# Oscillator_Core_Sch.net
KiCad netlist of a schematic drawn in EAGLE
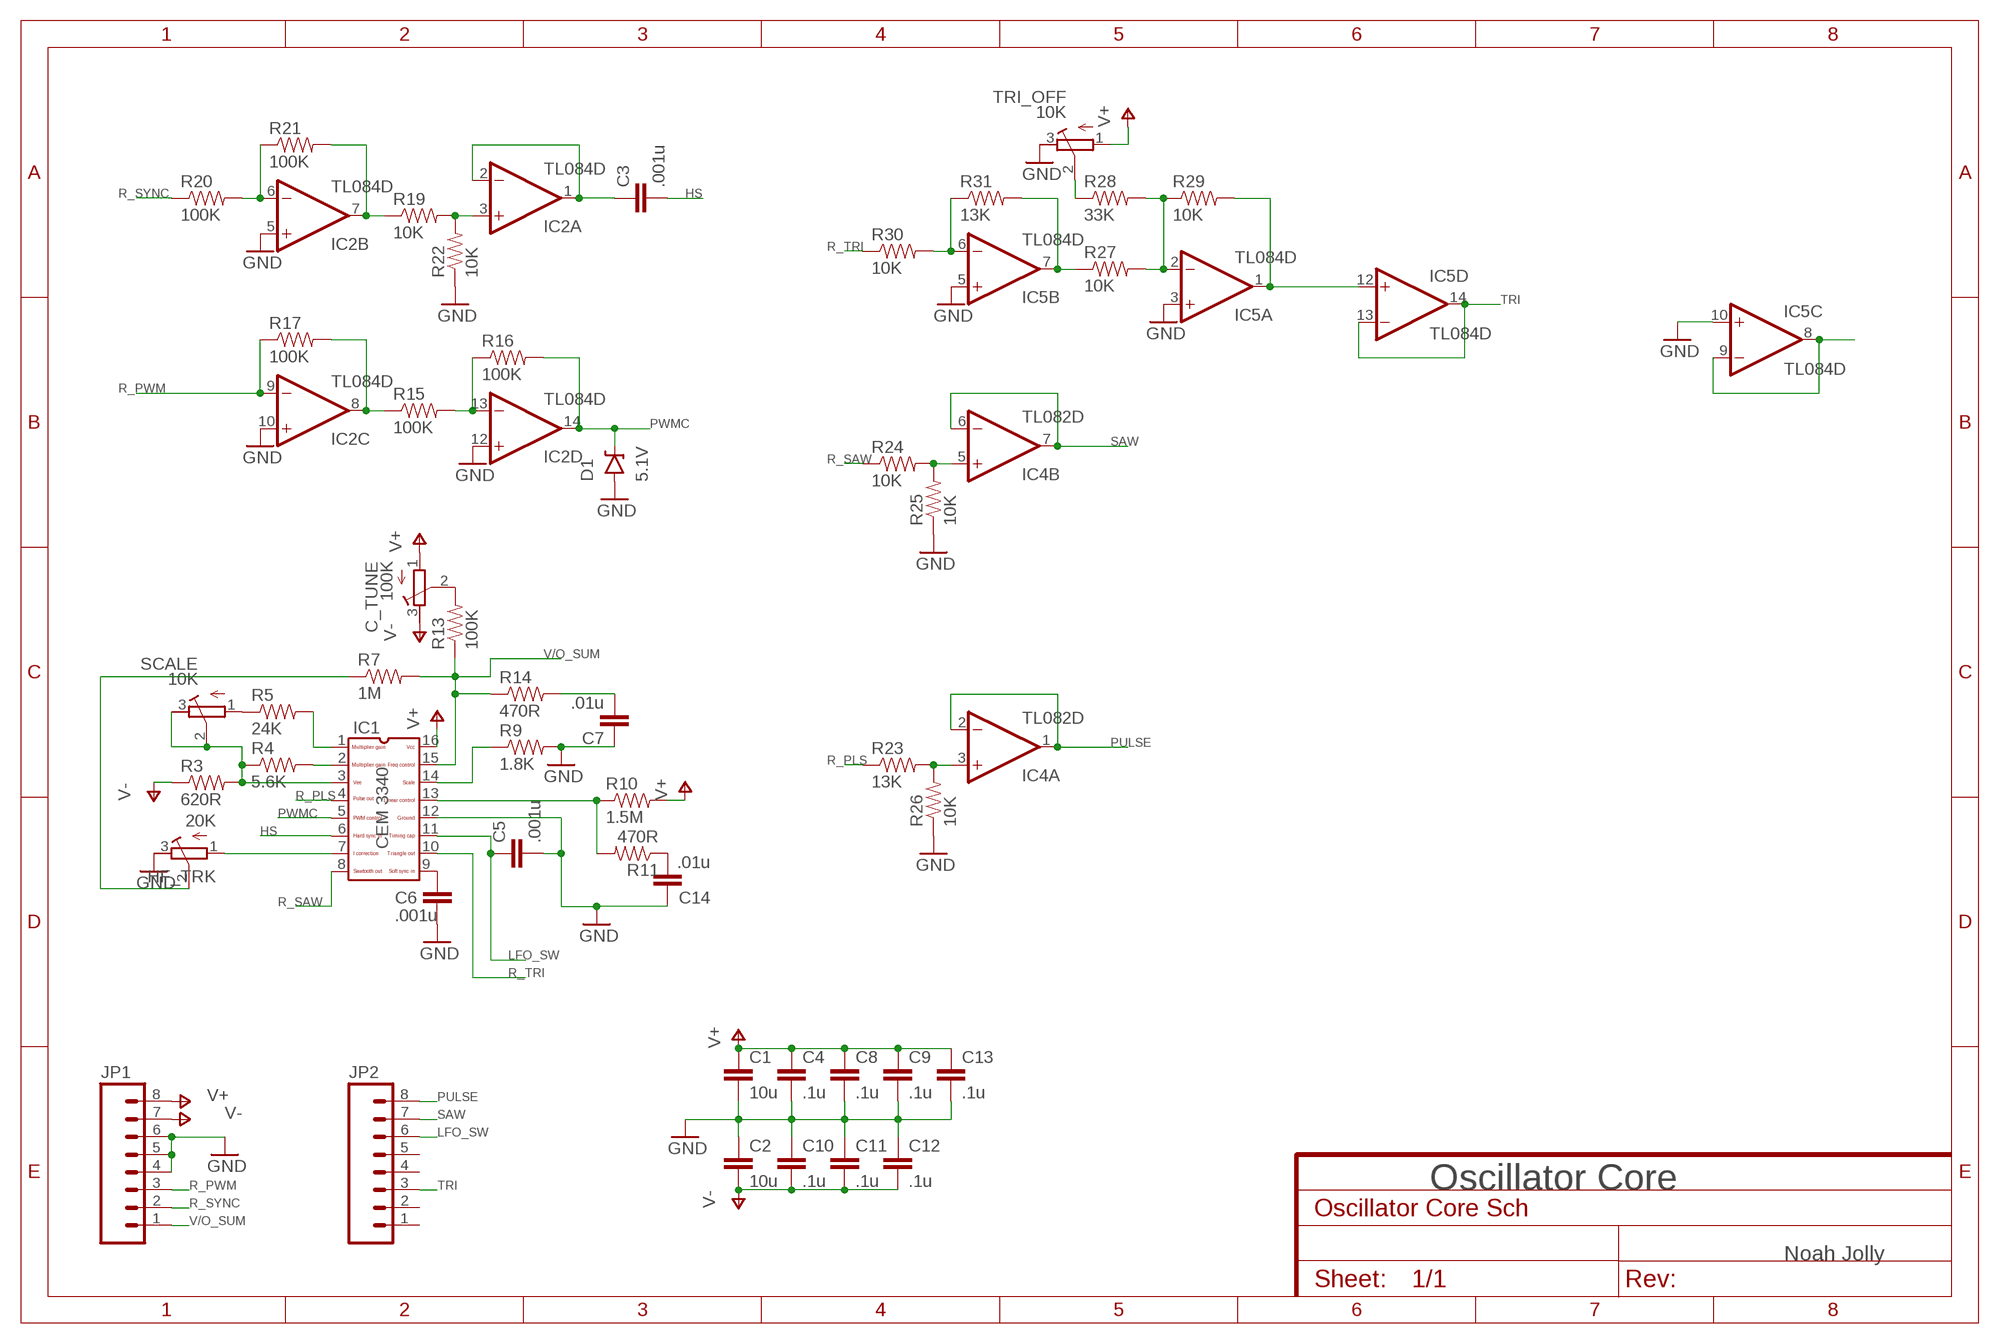
[diagram p0: schematic, sheet 1]

(export (version "E")
  (design (tool "Eeschema 10.0.6"))
  (components
    (comp (ref "C1")
      (value "10u")
      (footprint "eagle-import:1206")
      (libsource (lib "eagle-import") (part "CAP1206"))
    )
    (comp (ref "C2")
      (value "10u")
      (footprint "eagle-import:1206")
      (libsource (lib "eagle-import") (part "CAP1206"))
    )
    (comp (ref "C3")
      (value ".001u")
      (footprint "eagle-import:0805")
      (libsource (lib "eagle-import") (part "CAP0805"))
    )
    (comp (ref "C4")
      (value ".1u")
      (footprint "eagle-import:0805")
      (libsource (lib "eagle-import") (part "CAP0805"))
    )
    (comp (ref "C5")
      (value ".001u")
      (footprint "eagle-import:CAP-PTH-5MM")
      (libsource (lib "eagle-import") (part "SparkFun-Passives_CAPPTH1"))
    )
    (comp (ref "C6")
      (value ".001u")
      (footprint "eagle-import:0805")
      (libsource (lib "eagle-import") (part "CAP0805"))
    )
    (comp (ref "C7")
      (value ".01u")
      (footprint "eagle-import:0805")
      (libsource (lib "eagle-import") (part "CAP0805"))
    )
    (comp (ref "C8")
      (value ".1u")
      (footprint "eagle-import:0805")
      (libsource (lib "eagle-import") (part "CAP0805"))
    )
    (comp (ref "C9")
      (value ".1u")
      (footprint "eagle-import:0805")
      (libsource (lib "eagle-import") (part "CAP0805"))
    )
    (comp (ref "C10")
      (value ".1u")
      (footprint "eagle-import:0805")
      (libsource (lib "eagle-import") (part "CAP0805"))
    )
    (comp (ref "C11")
      (value ".1u")
      (footprint "eagle-import:0805")
      (libsource (lib "eagle-import") (part "CAP0805"))
    )
    (comp (ref "C12")
      (value ".1u")
      (footprint "eagle-import:0805")
      (libsource (lib "eagle-import") (part "CAP0805"))
    )
    (comp (ref "C13")
      (value ".1u")
      (footprint "eagle-import:0805")
      (libsource (lib "eagle-import") (part "CAP0805"))
    )
    (comp (ref "C14")
      (value ".01u")
      (footprint "eagle-import:0805")
      (libsource (lib "eagle-import") (part "CAP0805"))
    )
    (comp (ref "C_TUNE")
      (value "100K")
      (footprint "eagle-import:RTRIM3296Y")
      (libsource (lib "eagle-import") (part "R-TRIMM3296Y"))
    )
    (comp (ref "D1")
      (value "5.1V")
      (footprint "eagle-import:SOD-123")
      (libsource (lib "eagle-import") (part "DIODE-ZENER16V"))
    )
    (comp (ref "HF_TRK")
      (value "20K")
      (footprint "eagle-import:RTRIM3296Y")
      (libsource (lib "eagle-import") (part "R-TRIMM3296Y"))
    )
    (comp (ref "IC1")
      (value "CEM3340")
      (footprint "eagle-import:DIL16")
      (libsource (lib "eagle-import") (part "CEM3340"))
    )
    (comp (ref "IC2")
      (value "TL084D")
      (footprint "eagle-import:SO14")
      (libsource (lib "eagle-import") (part "TL084D"))
    )
    (comp (ref "IC4")
      (value "TL082D")
      (footprint "eagle-import:SO08")
      (libsource (lib "eagle-import") (part "TL082D"))
    )
    (comp (ref "IC5")
      (value "TL084D")
      (footprint "eagle-import:SO14")
      (libsource (lib "eagle-import") (part "TL084D"))
    )
    (comp (ref "JP1")
      (value "M08")
      (footprint "eagle-import:1X08_ROUND")
      (libsource (lib "eagle-import") (part "M08"))
    )
    (comp (ref "JP2")
      (value "M08")
      (footprint "eagle-import:1X08_ROUND")
      (libsource (lib "eagle-import") (part "M08"))
    )
    (comp (ref "R3")
      (value "620R")
      (footprint "eagle-import:0805@1")
      (libsource (lib "eagle-import") (part "RESISTOR0805-RES"))
    )
    (comp (ref "R4")
      (value "5.6K")
      (footprint "eagle-import:0805@1")
      (libsource (lib "eagle-import") (part "RESISTOR0805-RES"))
    )
    (comp (ref "R5")
      (value "24K")
      (footprint "eagle-import:0805@1")
      (libsource (lib "eagle-import") (part "RESISTOR0805-RES"))
    )
    (comp (ref "R7")
      (value "1M")
      (footprint "eagle-import:0805@1")
      (libsource (lib "eagle-import") (part "RESISTOR0805-RES"))
    )
    (comp (ref "R9")
      (value "1.8K")
      (footprint "eagle-import:0805@1")
      (libsource (lib "eagle-import") (part "RESISTOR0805-RES"))
    )
    (comp (ref "R10")
      (value "1.5M")
      (footprint "eagle-import:0805@1")
      (libsource (lib "eagle-import") (part "RESISTOR0805-RES"))
    )
    (comp (ref "R11")
      (value "470R")
      (footprint "eagle-import:0805@1")
      (libsource (lib "eagle-import") (part "RESISTOR0805-RES"))
    )
    (comp (ref "R13")
      (value "100K")
      (footprint "eagle-import:0805@1")
      (libsource (lib "eagle-import") (part "RESISTOR0805-RES"))
    )
    (comp (ref "R14")
      (value "470R")
      (footprint "eagle-import:0805@1")
      (libsource (lib "eagle-import") (part "RESISTOR0805-RES"))
    )
    (comp (ref "R15")
      (value "100K")
      (footprint "eagle-import:0805@1")
      (libsource (lib "eagle-import") (part "RESISTOR0805-RES"))
    )
    (comp (ref "R16")
      (value "100K")
      (footprint "eagle-import:0805@1")
      (libsource (lib "eagle-import") (part "RESISTOR0805-RES"))
    )
    (comp (ref "R17")
      (value "100K")
      (footprint "eagle-import:0805@1")
      (libsource (lib "eagle-import") (part "RESISTOR0805-RES"))
    )
    (comp (ref "R19")
      (value "10K")
      (footprint "eagle-import:0805@1")
      (libsource (lib "eagle-import") (part "RESISTOR0805-RES"))
    )
    (comp (ref "R20")
      (value "100K")
      (footprint "eagle-import:0805@1")
      (libsource (lib "eagle-import") (part "RESISTOR0805-RES"))
    )
    (comp (ref "R21")
      (value "100K")
      (footprint "eagle-import:0805@1")
      (libsource (lib "eagle-import") (part "RESISTOR0805-RES"))
    )
    (comp (ref "R22")
      (value "10K")
      (footprint "eagle-import:0805@1")
      (libsource (lib "eagle-import") (part "RESISTOR0805-RES"))
    )
    (comp (ref "R23")
      (value "13K")
      (footprint "eagle-import:0805@1")
      (libsource (lib "eagle-import") (part "RESISTOR0805-RES"))
    )
    (comp (ref "R24")
      (value "10K")
      (footprint "eagle-import:0805@1")
      (libsource (lib "eagle-import") (part "RESISTOR0805-RES"))
    )
    (comp (ref "R25")
      (value "10K")
      (footprint "eagle-import:0805@1")
      (libsource (lib "eagle-import") (part "RESISTOR0805-RES"))
    )
    (comp (ref "R26")
      (value "10K")
      (footprint "eagle-import:0805@1")
      (libsource (lib "eagle-import") (part "RESISTOR0805-RES"))
    )
    (comp (ref "R27")
      (value "10K")
      (footprint "eagle-import:0805@1")
      (libsource (lib "eagle-import") (part "RESISTOR0805-RES"))
    )
    (comp (ref "R28")
      (value "33K")
      (footprint "eagle-import:0805@1")
      (libsource (lib "eagle-import") (part "RESISTOR0805-RES"))
    )
    (comp (ref "R29")
      (value "10K")
      (footprint "eagle-import:0805@1")
      (libsource (lib "eagle-import") (part "RESISTOR0805-RES"))
    )
    (comp (ref "R30")
      (value "10K")
      (footprint "eagle-import:0805@1")
      (libsource (lib "eagle-import") (part "RESISTOR0805-RES"))
    )
    (comp (ref "R31")
      (value "13K")
      (footprint "eagle-import:0805@1")
      (libsource (lib "eagle-import") (part "RESISTOR0805-RES"))
    )
    (comp (ref "SCALE")
      (value "10K")
      (footprint "eagle-import:RTRIM3296Y")
      (libsource (lib "eagle-import") (part "R-TRIMM3296Y"))
    )
    (comp (ref "TRI_OFF")
      (value "10K")
      (footprint "eagle-import:RTRIM3296Y")
      (libsource (lib "eagle-import") (part "R-TRIMM3296Y"))
    )
  )
  (nets
    (net (code "1") (name "/HS") (class "Default")
      (node (ref "C3") (pin "2") (pinfunction "2_2") (pintype "passive"))
      (node (ref "IC1") (pin "6") (pinfunction "6_6") (pintype "input"))
    )
    (net (code "2") (name "/LFO_SW") (class "Default")
      (node (ref "C5") (pin "1") (pinfunction "1_1") (pintype "passive"))
      (node (ref "IC1") (pin "11") (pinfunction "11_11") (pintype "bidirectional"))
      (node (ref "JP2") (pin "6") (pinfunction "6_6") (pintype "passive"))
    )
    (net (code "3") (name "/PULSE") (class "Default")
      (node (ref "IC4") (pin "1") (pinfunction "OUT_1") (pintype "output"))
      (node (ref "IC4") (pin "2") (pinfunction "-IN_2") (pintype "input"))
      (node (ref "JP2") (pin "8") (pinfunction "8_8") (pintype "passive"))
    )
    (net (code "4") (name "/PWMC") (class "Default")
      (node (ref "D1") (pin "C") (pinfunction "C_C") (pintype "passive"))
      (node (ref "IC1") (pin "5") (pinfunction "5_5") (pintype "input"))
      (node (ref "IC2") (pin "14") (pinfunction "OUT_14") (pintype "output"))
      (node (ref "R16") (pin "2") (pinfunction "2_2") (pintype "passive"))
    )
    (net (code "5") (name "/R_PLS") (class "Default")
      (node (ref "IC1") (pin "4") (pinfunction "4_4") (pintype "output"))
      (node (ref "R23") (pin "1") (pinfunction "1_1") (pintype "passive"))
    )
    (net (code "6") (name "/R_PWM") (class "Default")
      (node (ref "IC2") (pin "9") (pinfunction "-IN_9") (pintype "input"))
      (node (ref "JP1") (pin "3") (pinfunction "3_3") (pintype "passive"))
      (node (ref "R17") (pin "1") (pinfunction "1_1") (pintype "passive"))
    )
    (net (code "7") (name "/R_SAW") (class "Default")
      (node (ref "IC1") (pin "8") (pinfunction "8_8") (pintype "output"))
      (node (ref "R24") (pin "1") (pinfunction "1_1") (pintype "passive"))
    )
    (net (code "8") (name "/R_SYNC") (class "Default")
      (node (ref "JP1") (pin "2") (pinfunction "2_2") (pintype "passive"))
      (node (ref "R20") (pin "1") (pinfunction "1_1") (pintype "passive"))
    )
    (net (code "9") (name "/R_TRI") (class "Default")
      (node (ref "IC1") (pin "10") (pinfunction "10_10") (pintype "output"))
      (node (ref "R30") (pin "1") (pinfunction "1_1") (pintype "passive"))
    )
    (net (code "10") (name "/SAW") (class "Default")
      (node (ref "IC4") (pin "6") (pinfunction "-IN_6") (pintype "input"))
      (node (ref "IC4") (pin "7") (pinfunction "OUT_7") (pintype "output"))
      (node (ref "JP2") (pin "7") (pinfunction "7_7") (pintype "passive"))
    )
    (net (code "11") (name "/TRI") (class "Default")
      (node (ref "IC5") (pin "13") (pinfunction "-IN_13") (pintype "input"))
      (node (ref "IC5") (pin "14") (pinfunction "OUT_14") (pintype "output"))
      (node (ref "JP2") (pin "3") (pinfunction "3_3") (pintype "passive"))
    )
    (net (code "12") (name "/V{slash}O_SUM") (class "Default")
      (node (ref "IC1") (pin "15") (pinfunction "15_15") (pintype "input"))
      (node (ref "JP1") (pin "1") (pinfunction "1_1") (pintype "passive"))
      (node (ref "R13") (pin "1") (pinfunction "1_1") (pintype "passive"))
      (node (ref "R14") (pin "1") (pinfunction "1_1") (pintype "passive"))
      (node (ref "R7") (pin "2") (pinfunction "2_2") (pintype "passive"))
    )
    (net (code "13") (name "GND") (class "Default")
      (node (ref "C1") (pin "2") (pinfunction "2_2") (pintype "passive"))
      (node (ref "C10") (pin "1") (pinfunction "1_1") (pintype "passive"))
      (node (ref "C11") (pin "1") (pinfunction "1_1") (pintype "passive"))
      (node (ref "C12") (pin "1") (pinfunction "1_1") (pintype "passive"))
      (node (ref "C13") (pin "2") (pinfunction "2_2") (pintype "passive"))
      (node (ref "C14") (pin "1") (pinfunction "1_1") (pintype "passive"))
      (node (ref "C2") (pin "1") (pinfunction "1_1") (pintype "passive"))
      (node (ref "C4") (pin "2") (pinfunction "2_2") (pintype "passive"))
      (node (ref "C5") (pin "2") (pinfunction "2_2") (pintype "passive"))
      (node (ref "C6") (pin "2") (pinfunction "2_2") (pintype "passive"))
      (node (ref "C7") (pin "1") (pinfunction "1_1") (pintype "passive"))
      (node (ref "C8") (pin "2") (pinfunction "2_2") (pintype "passive"))
      (node (ref "C9") (pin "2") (pinfunction "2_2") (pintype "passive"))
      (node (ref "D1") (pin "A") (pinfunction "A_A") (pintype "passive"))
      (node (ref "HF_TRK") (pin "3") (pinfunction "E_3") (pintype "passive"))
      (node (ref "IC1") (pin "12") (pinfunction "12_12") (pintype "power_in"))
      (node (ref "IC2") (pin "10") (pinfunction "+IN_10") (pintype "input"))
      (node (ref "IC2") (pin "12") (pinfunction "+IN_12") (pintype "input"))
      (node (ref "IC2") (pin "5") (pinfunction "+IN_5") (pintype "input"))
      (node (ref "IC5") (pin "10") (pinfunction "+IN_10") (pintype "input"))
      (node (ref "IC5") (pin "3") (pinfunction "+IN_3") (pintype "input"))
      (node (ref "IC5") (pin "5") (pinfunction "+IN_5") (pintype "input"))
      (node (ref "JP1") (pin "4") (pinfunction "4_4") (pintype "passive"))
      (node (ref "JP1") (pin "5") (pinfunction "5_5") (pintype "passive"))
      (node (ref "JP1") (pin "6") (pinfunction "6_6") (pintype "passive"))
      (node (ref "R22") (pin "1") (pinfunction "1_1") (pintype "passive"))
      (node (ref "R25") (pin "1") (pinfunction "1_1") (pintype "passive"))
      (node (ref "R26") (pin "1") (pinfunction "1_1") (pintype "passive"))
      (node (ref "R9") (pin "2") (pinfunction "2_2") (pintype "passive"))
      (node (ref "TRI_OFF") (pin "3") (pinfunction "E_3") (pintype "passive"))
    )
    (net (code "14") (name "Net-(C6-Pad1)") (class "Default")
      (node (ref "C6") (pin "1") (pinfunction "1_1") (pintype "passive"))
      (node (ref "IC1") (pin "9") (pinfunction "9_9") (pintype "input"))
    )
    (net (code "15") (name "Net-(C7-Pad2)") (class "Default")
      (node (ref "C7") (pin "2") (pinfunction "2_2") (pintype "passive"))
      (node (ref "R14") (pin "2") (pinfunction "2_2") (pintype "passive"))
    )
    (net (code "16") (name "Net-(C14-Pad2)") (class "Default")
      (node (ref "C14") (pin "2") (pinfunction "2_2") (pintype "passive"))
      (node (ref "R11") (pin "1") (pinfunction "1_1") (pintype "passive"))
    )
    (net (code "17") (name "Net-(C_TUNE-S)") (class "Default")
      (node (ref "C_TUNE") (pin "2") (pinfunction "S_2") (pintype "passive"))
      (node (ref "R13") (pin "2") (pinfunction "2_2") (pintype "passive"))
    )
    (net (code "18") (name "Net-(HF_TRK-A)") (class "Default")
      (node (ref "HF_TRK") (pin "1") (pinfunction "A_1") (pintype "passive"))
      (node (ref "IC1") (pin "7") (pinfunction "7_7") (pintype "bidirectional"))
    )
    (net (code "19") (name "Net-(HF_TRK-S)") (class "Default")
      (node (ref "HF_TRK") (pin "2") (pinfunction "S_2") (pintype "passive"))
      (node (ref "R7") (pin "1") (pinfunction "1_1") (pintype "passive"))
    )
    (net (code "20") (name "Net-(IC1-Pad1)") (class "Default")
      (node (ref "IC1") (pin "1") (pinfunction "1_1") (pintype "bidirectional"))
      (node (ref "R5") (pin "2") (pinfunction "2_2") (pintype "passive"))
    )
    (net (code "21") (name "Net-(IC1-Pad2)") (class "Default")
      (node (ref "IC1") (pin "2") (pinfunction "2_2") (pintype "bidirectional"))
      (node (ref "R4") (pin "2") (pinfunction "2_2") (pintype "passive"))
    )
    (net (code "22") (name "Net-(IC1-Pad13)") (class "Default")
      (node (ref "IC1") (pin "13") (pinfunction "13_13") (pintype "input"))
      (node (ref "R10") (pin "1") (pinfunction "1_1") (pintype "passive"))
      (node (ref "R11") (pin "2") (pinfunction "2_2") (pintype "passive"))
    )
    (net (code "23") (name "Net-(IC1-Pad14)") (class "Default")
      (node (ref "IC1") (pin "14") (pinfunction "14_14") (pintype "input"))
      (node (ref "R9") (pin "1") (pinfunction "1_1") (pintype "passive"))
    )
    (net (code "24") (name "Net-(IC2A-+IN)") (class "Default")
      (node (ref "IC2") (pin "3") (pinfunction "+IN_3") (pintype "input"))
      (node (ref "R19") (pin "2") (pinfunction "2_2") (pintype "passive"))
      (node (ref "R22") (pin "2") (pinfunction "2_2") (pintype "passive"))
    )
    (net (code "25") (name "Net-(IC2A--IN)") (class "Default")
      (node (ref "C3") (pin "1") (pinfunction "1_1") (pintype "passive"))
      (node (ref "IC2") (pin "1") (pinfunction "OUT_1") (pintype "output"))
      (node (ref "IC2") (pin "2") (pinfunction "-IN_2") (pintype "input"))
    )
    (net (code "26") (name "Net-(IC2B--IN)") (class "Default")
      (node (ref "IC2") (pin "6") (pinfunction "-IN_6") (pintype "input"))
      (node (ref "R20") (pin "2") (pinfunction "2_2") (pintype "passive"))
      (node (ref "R21") (pin "1") (pinfunction "1_1") (pintype "passive"))
    )
    (net (code "27") (name "Net-(IC2B-OUT)") (class "Default")
      (node (ref "IC2") (pin "7") (pinfunction "OUT_7") (pintype "output"))
      (node (ref "R19") (pin "1") (pinfunction "1_1") (pintype "passive"))
      (node (ref "R21") (pin "2") (pinfunction "2_2") (pintype "passive"))
    )
    (net (code "28") (name "Net-(IC2C-OUT)") (class "Default")
      (node (ref "IC2") (pin "8") (pinfunction "OUT_8") (pintype "output"))
      (node (ref "R15") (pin "1") (pinfunction "1_1") (pintype "passive"))
      (node (ref "R17") (pin "2") (pinfunction "2_2") (pintype "passive"))
    )
    (net (code "29") (name "Net-(IC2D--IN)") (class "Default")
      (node (ref "IC2") (pin "13") (pinfunction "-IN_13") (pintype "input"))
      (node (ref "R15") (pin "2") (pinfunction "2_2") (pintype "passive"))
      (node (ref "R16") (pin "1") (pinfunction "1_1") (pintype "passive"))
    )
    (net (code "30") (name "Net-(IC4A-+IN)") (class "Default")
      (node (ref "IC4") (pin "3") (pinfunction "+IN_3") (pintype "input"))
      (node (ref "R23") (pin "2") (pinfunction "2_2") (pintype "passive"))
      (node (ref "R26") (pin "2") (pinfunction "2_2") (pintype "passive"))
    )
    (net (code "31") (name "Net-(IC4B-+IN)") (class "Default")
      (node (ref "IC4") (pin "5") (pinfunction "+IN_5") (pintype "input"))
      (node (ref "R24") (pin "2") (pinfunction "2_2") (pintype "passive"))
      (node (ref "R25") (pin "2") (pinfunction "2_2") (pintype "passive"))
    )
    (net (code "32") (name "Net-(IC5A--IN)") (class "Default")
      (node (ref "IC5") (pin "2") (pinfunction "-IN_2") (pintype "input"))
      (node (ref "R27") (pin "2") (pinfunction "2_2") (pintype "passive"))
      (node (ref "R28") (pin "2") (pinfunction "2_2") (pintype "passive"))
      (node (ref "R29") (pin "1") (pinfunction "1_1") (pintype "passive"))
    )
    (net (code "33") (name "Net-(IC5A-OUT)") (class "Default")
      (node (ref "IC5") (pin "1") (pinfunction "OUT_1") (pintype "output"))
      (node (ref "IC5") (pin "12") (pinfunction "+IN_12") (pintype "input"))
      (node (ref "R29") (pin "2") (pinfunction "2_2") (pintype "passive"))
    )
    (net (code "34") (name "Net-(IC5B--IN)") (class "Default")
      (node (ref "IC5") (pin "6") (pinfunction "-IN_6") (pintype "input"))
      (node (ref "R30") (pin "2") (pinfunction "2_2") (pintype "passive"))
      (node (ref "R31") (pin "1") (pinfunction "1_1") (pintype "passive"))
    )
    (net (code "35") (name "Net-(IC5B-OUT)") (class "Default")
      (node (ref "IC5") (pin "7") (pinfunction "OUT_7") (pintype "output"))
      (node (ref "R27") (pin "1") (pinfunction "1_1") (pintype "passive"))
      (node (ref "R31") (pin "2") (pinfunction "2_2") (pintype "passive"))
    )
    (net (code "36") (name "Net-(IC5C--IN)") (class "Default")
      (node (ref "IC5") (pin "8") (pinfunction "OUT_8") (pintype "output"))
      (node (ref "IC5") (pin "9") (pinfunction "-IN_9") (pintype "input"))
    )
    (net (code "37") (name "Net-(SCALE-A)") (class "Default")
      (node (ref "R5") (pin "1") (pinfunction "1_1") (pintype "passive"))
      (node (ref "SCALE") (pin "1") (pinfunction "A_1") (pintype "passive"))
    )
    (net (code "38") (name "Net-(SCALE-E)") (class "Default")
      (node (ref "IC1") (pin "3") (pinfunction "3_3") (pintype "power_in"))
      (node (ref "R3") (pin "2") (pinfunction "2_2") (pintype "passive"))
      (node (ref "R4") (pin "1") (pinfunction "1_1") (pintype "passive"))
      (node (ref "SCALE") (pin "2") (pinfunction "S_2") (pintype "passive"))
      (node (ref "SCALE") (pin "3") (pinfunction "E_3") (pintype "passive"))
    )
    (net (code "39") (name "Net-(TRI_OFF-S)") (class "Default")
      (node (ref "R28") (pin "1") (pinfunction "1_1") (pintype "passive"))
      (node (ref "TRI_OFF") (pin "2") (pinfunction "S_2") (pintype "passive"))
    )
    (net (code "40") (name "V+") (class "Default")
      (node (ref "C1") (pin "1") (pinfunction "1_1") (pintype "passive"))
      (node (ref "C13") (pin "1") (pinfunction "1_1") (pintype "passive"))
      (node (ref "C4") (pin "1") (pinfunction "1_1") (pintype "passive"))
      (node (ref "C8") (pin "1") (pinfunction "1_1") (pintype "passive"))
      (node (ref "C9") (pin "1") (pinfunction "1_1") (pintype "passive"))
      (node (ref "C_TUNE") (pin "1") (pinfunction "A_1") (pintype "passive"))
      (node (ref "IC1") (pin "16") (pinfunction "16_16") (pintype "power_in"))
      (node (ref "JP1") (pin "8") (pinfunction "8_8") (pintype "passive"))
      (node (ref "R10") (pin "2") (pinfunction "2_2") (pintype "passive"))
      (node (ref "TRI_OFF") (pin "1") (pinfunction "A_1") (pintype "passive"))
    )
    (net (code "41") (name "V-") (class "Default")
      (node (ref "C10") (pin "2") (pinfunction "2_2") (pintype "passive"))
      (node (ref "C11") (pin "2") (pinfunction "2_2") (pintype "passive"))
      (node (ref "C12") (pin "2") (pinfunction "2_2") (pintype "passive"))
      (node (ref "C2") (pin "2") (pinfunction "2_2") (pintype "passive"))
      (node (ref "C_TUNE") (pin "3") (pinfunction "E_3") (pintype "passive"))
      (node (ref "JP1") (pin "7") (pinfunction "7_7") (pintype "passive"))
      (node (ref "R3") (pin "1") (pinfunction "1_1") (pintype "passive"))
    )
    (net (code "42") (name "unconnected-(JP2-Pad1)") (class "Default")
      (node (ref "JP2") (pin "1") (pinfunction "1_1") (pintype "passive"))
    )
    (net (code "43") (name "unconnected-(JP2-Pad2)") (class "Default")
      (node (ref "JP2") (pin "2") (pinfunction "2_2") (pintype "passive"))
    )
    (net (code "44") (name "unconnected-(JP2-Pad4)") (class "Default")
      (node (ref "JP2") (pin "4") (pinfunction "4_4") (pintype "passive"))
    )
    (net (code "45") (name "unconnected-(JP2-Pad5)") (class "Default")
      (node (ref "JP2") (pin "5") (pinfunction "5_5") (pintype "passive"))
    )
  )
)
